# 3_phase_NPC_inverter.net
KiCad netlist of a schematic drawn in Altium Designer
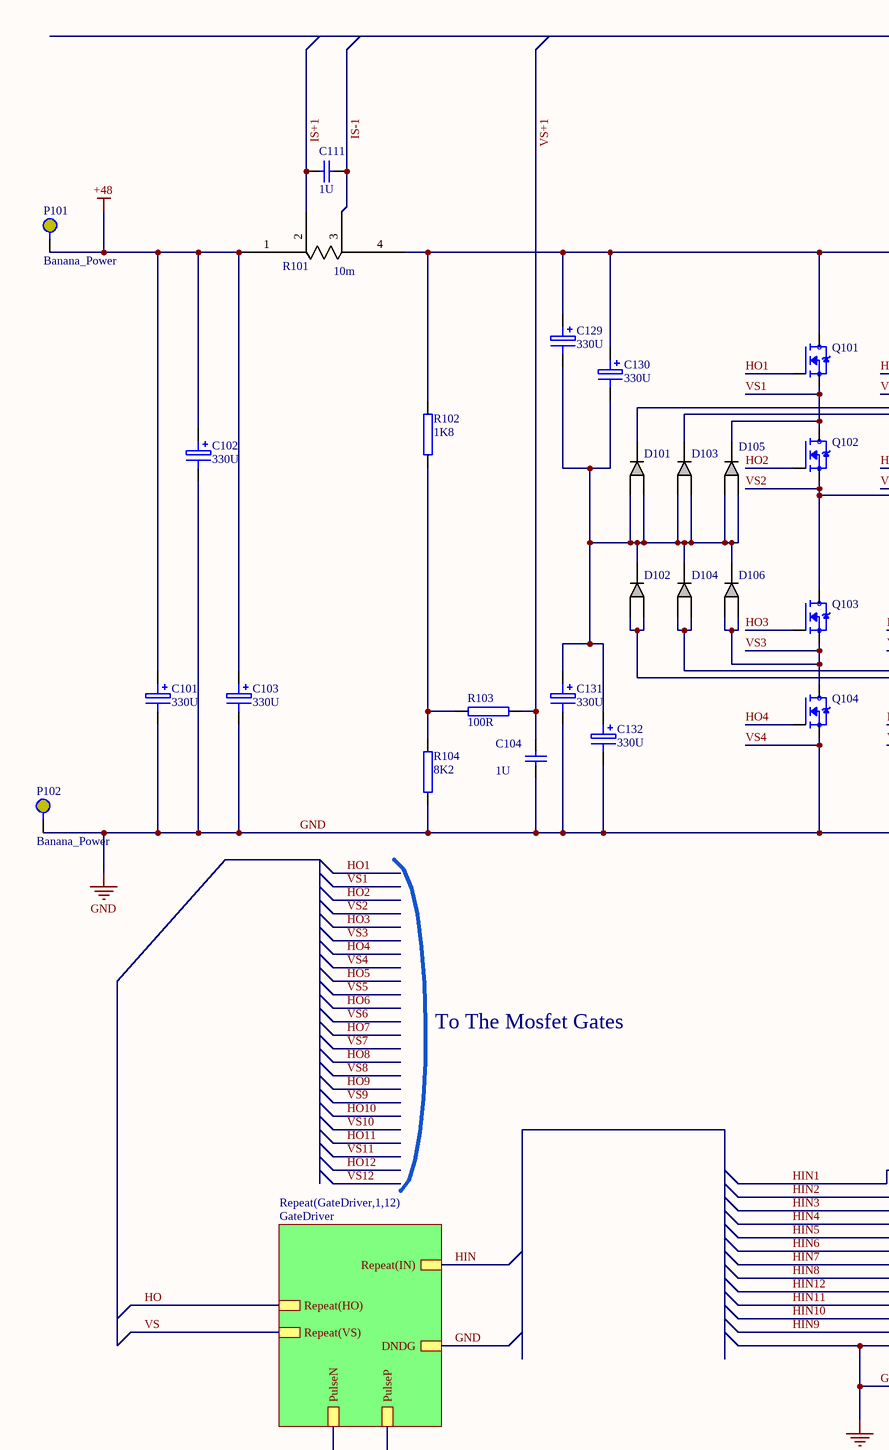
[diagram p0: 3 phase NPC inverter.SchDoc, top left]
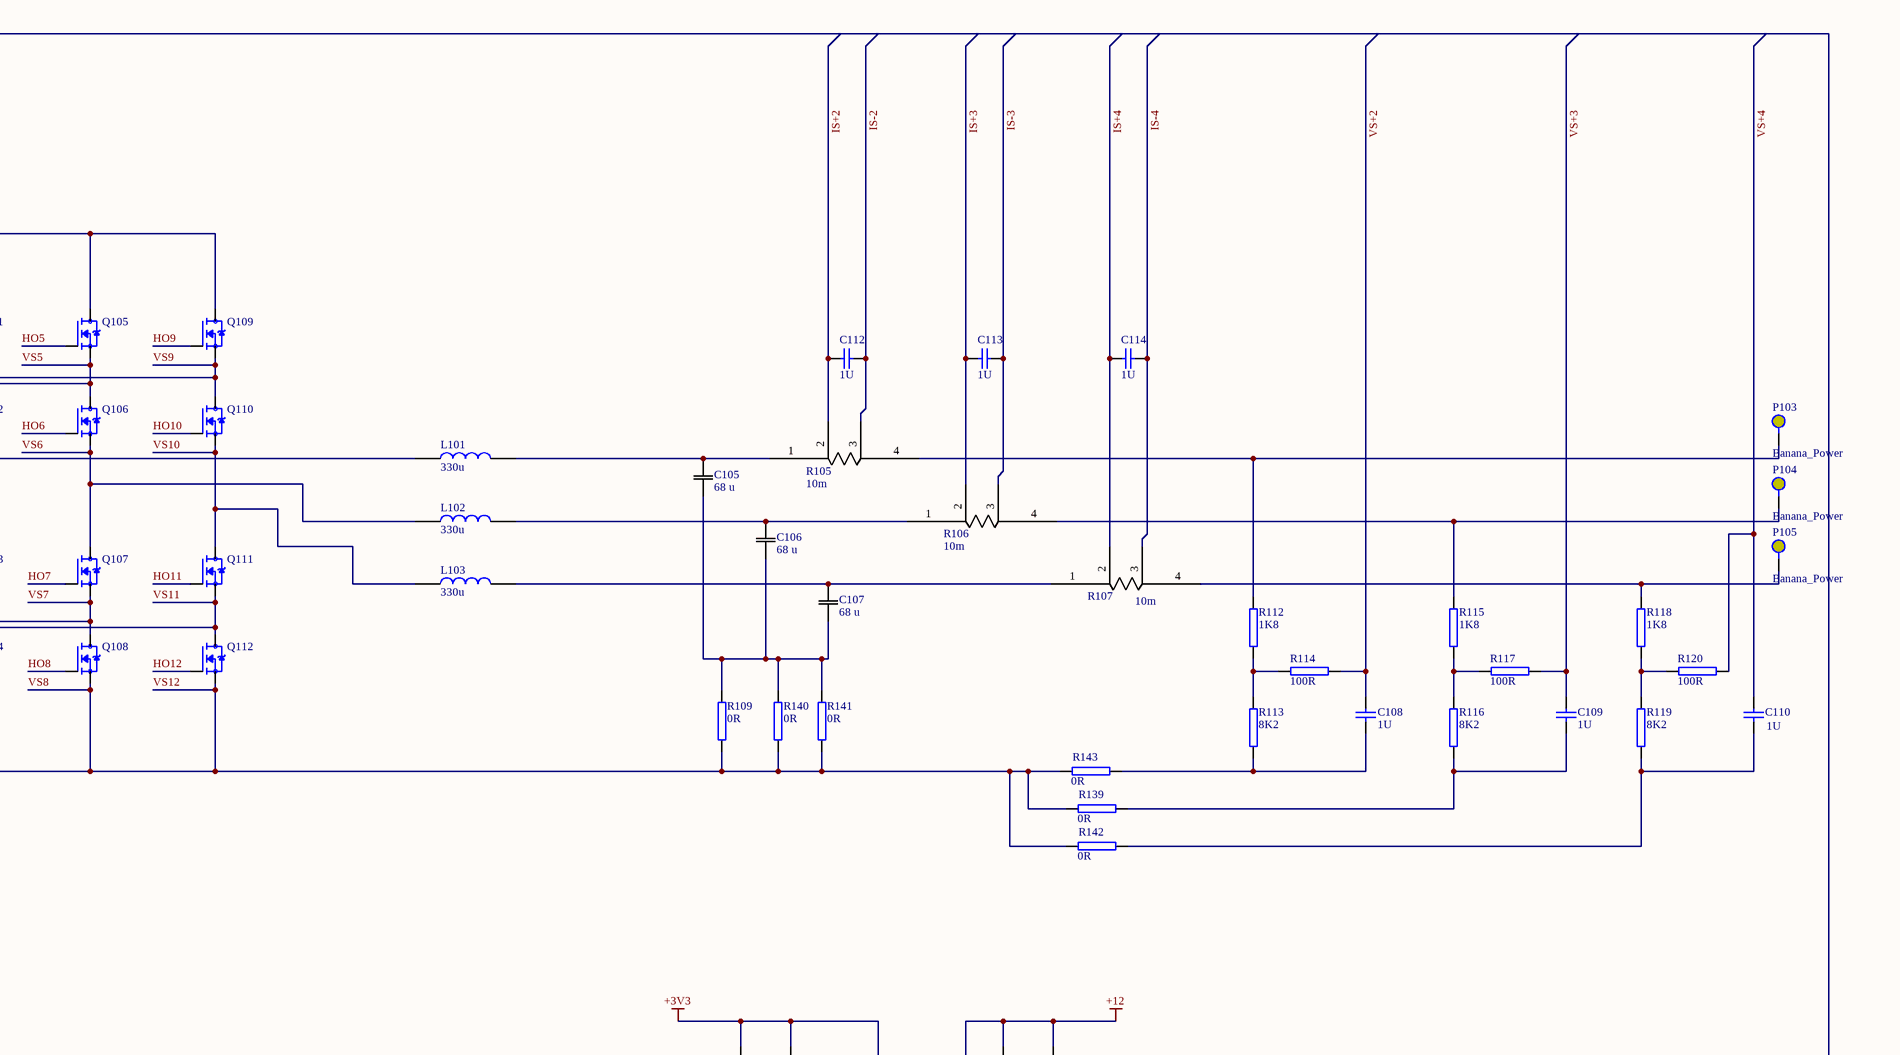
[diagram p1: 3 phase NPC inverter.SchDoc, top right]
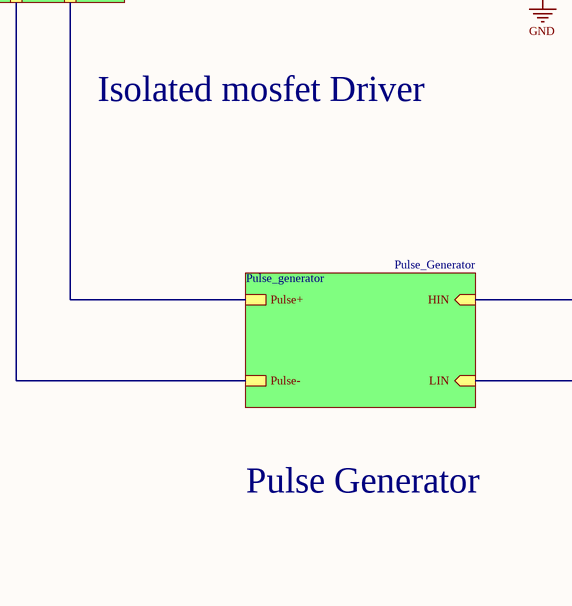
[diagram p2: 3 phase NPC inverter.SchDoc, bottom left]
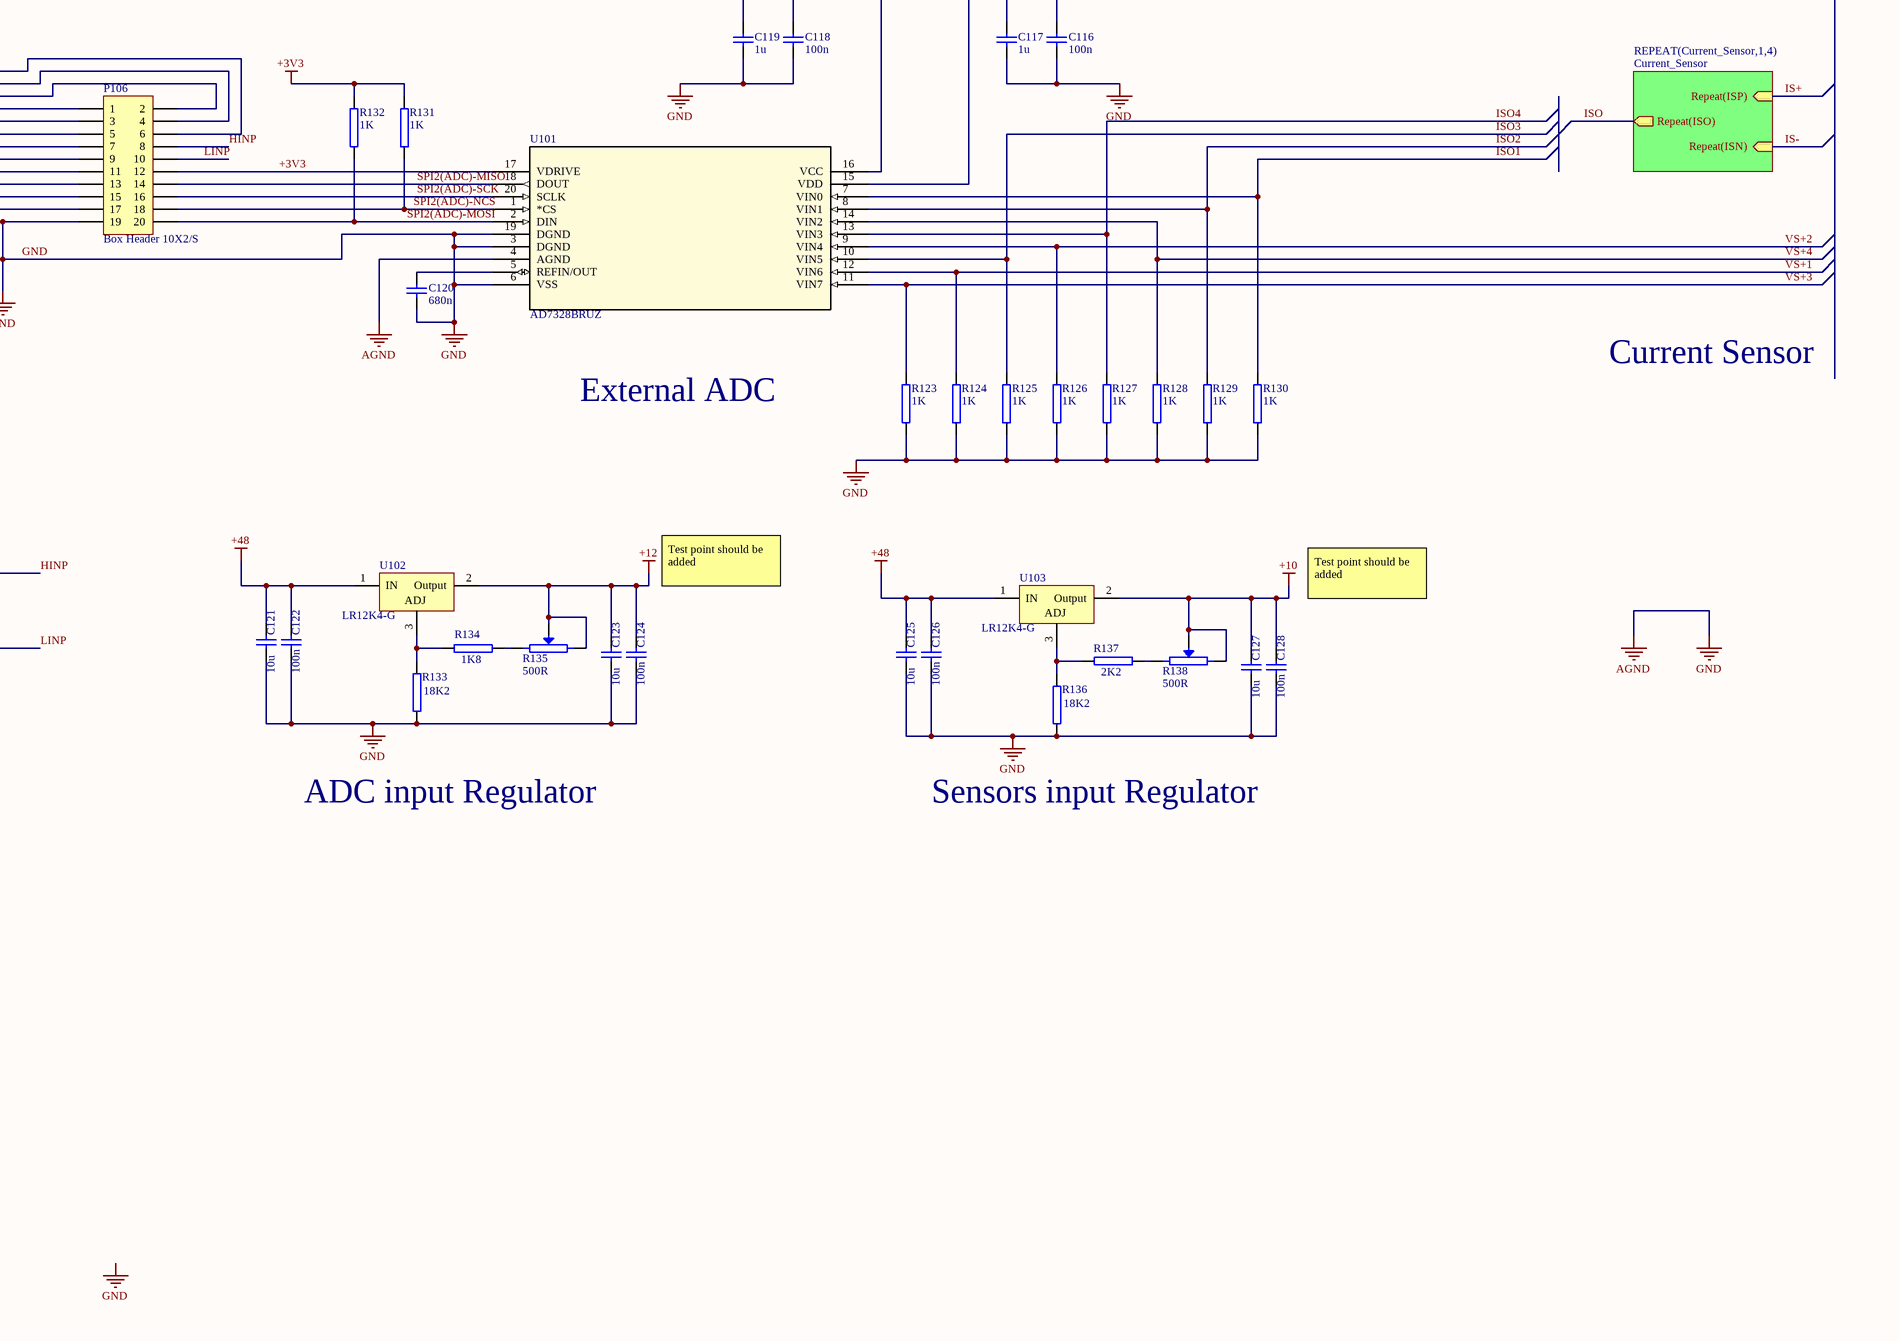
[diagram p3: 3 phase NPC inverter.SchDoc, bottom right]

(export (version "E")
  (design (tool "Eeschema 10.0.6"))
  (components
    (comp (ref "C101")
      (value "330U")
      (footprint "CAPP300-600_AUT")
      (description "Polarized Aluminum Capacitor, Through Hole, Pitch 300mil, Body 600mil (Dia)")
      (libsource (lib "Resistors and Capacitors") (part "CAPP300-600"))
    )
    (comp (ref "C102")
      (value "330U")
      (footprint "CAPP300-600_AUT")
      (description "Polarized Aluminum Capacitor, Through Hole, Pitch 300mil, Body 600mil (Dia)")
      (libsource (lib "Resistors and Capacitors") (part "CAPP300-600"))
    )
    (comp (ref "C103")
      (value "330U")
      (footprint "CAPP300-600_AUT")
      (description "Polarized Aluminum Capacitor, Through Hole, Pitch 300mil, Body 600mil (Dia)")
      (libsource (lib "Resistors and Capacitors") (part "CAPP300-600"))
    )
    (comp (ref "C104")
      (value "1U")
      (footprint "CAP_1206")
      (description "Non Polarized Capacitor, SMD, 1206")
      (libsource (lib "Resistors and Capacitors") (part "CAPN 1206"))
    )
    (comp (ref "C105")
      (value "68 u")
      (footprint "B32526R3686K000")
      (libsource (lib "ENEL709_Schematic_Library") (part "B32526R3686K000"))
    )
    (comp (ref "C106")
      (value "68 u")
      (footprint "B32526R3686K000")
      (libsource (lib "ENEL709_Schematic_Library") (part "B32526R3686K000"))
    )
    (comp (ref "C107")
      (value "68 u")
      (footprint "B32526R3686K000")
      (libsource (lib "ENEL709_Schematic_Library") (part "B32526R3686K000"))
    )
    (comp (ref "C108")
      (value "1U")
      (footprint "CAP_1206")
      (description "Non Polarized Capacitor, SMD, 1206")
      (libsource (lib "Resistors and Capacitors") (part "CAPN 1206"))
    )
    (comp (ref "C109")
      (value "1U")
      (footprint "CAP_1206")
      (description "Non Polarized Capacitor, SMD, 1206")
      (libsource (lib "Resistors and Capacitors") (part "CAPN 1206"))
    )
    (comp (ref "C110")
      (value "1U")
      (footprint "CAP_1206")
      (description "Non Polarized Capacitor, SMD, 1206")
      (libsource (lib "Resistors and Capacitors") (part "CAPN 1206"))
    )
    (comp (ref "C111")
      (value "1U")
      (footprint "CAP_1206")
      (description "Non Polarized Capacitor, SMD, 1206")
      (libsource (lib "Resistors and Capacitors") (part "CAPN 1206"))
    )
    (comp (ref "C112")
      (value "1U")
      (footprint "CAP_1206")
      (description "Non Polarized Capacitor, SMD, 1206")
      (libsource (lib "Resistors and Capacitors") (part "CAPN 1206"))
    )
    (comp (ref "C113")
      (value "1U")
      (footprint "CAP_1206")
      (description "Non Polarized Capacitor, SMD, 1206")
      (libsource (lib "Resistors and Capacitors") (part "CAPN 1206"))
    )
    (comp (ref "C114")
      (value "1U")
      (footprint "CAP_1206")
      (description "Non Polarized Capacitor, SMD, 1206")
      (libsource (lib "Resistors and Capacitors") (part "CAPN 1206"))
    )
    (comp (ref "C116")
      (value "100n")
      (footprint "CAP_1206")
      (description "Non Polarized Capacitor, SMD, 1206")
      (libsource (lib "Resistors and Capacitors") (part "CAPN 1206"))
    )
    (comp (ref "C117")
      (value "1u")
      (footprint "CAP_1206")
      (description "Non Polarized Capacitor, SMD, 1206")
      (libsource (lib "Resistors and Capacitors") (part "CAPN 1206"))
    )
    (comp (ref "C118")
      (value "100n")
      (footprint "CAP_1206")
      (description "Non Polarized Capacitor, SMD, 1206")
      (libsource (lib "Resistors and Capacitors") (part "CAPN 1206"))
    )
    (comp (ref "C119")
      (value "1u")
      (footprint "CAP_1206")
      (description "Non Polarized Capacitor, SMD, 1206")
      (libsource (lib "Resistors and Capacitors") (part "CAPN 1206"))
    )
    (comp (ref "C120")
      (value "680n")
      (footprint "CAP_1206")
      (description "Non Polarized Capacitor, SMD, 1206")
      (libsource (lib "Resistors and Capacitors") (part "CAPN 1206"))
    )
    (comp (ref "C121")
      (value "10u")
      (footprint "CAP_1206")
      (description "Non Polarized Capacitor, SMD, 1206")
      (libsource (lib "Resistors and Capacitors") (part "CAPN 1206"))
    )
    (comp (ref "C122")
      (value "100n")
      (footprint "CAP_1206")
      (description "Non Polarized Capacitor, SMD, 1206")
      (libsource (lib "Resistors and Capacitors") (part "CAPN 1206"))
    )
    (comp (ref "C123")
      (value "10u")
      (footprint "CAP_1206")
      (description "Non Polarized Capacitor, SMD, 1206")
      (libsource (lib "Resistors and Capacitors") (part "CAPN 1206"))
    )
    (comp (ref "C124")
      (value "100n")
      (footprint "CAP_1206")
      (description "Non Polarized Capacitor, SMD, 1206")
      (libsource (lib "Resistors and Capacitors") (part "CAPN 1206"))
    )
    (comp (ref "C125")
      (value "10u")
      (footprint "CAP_1206")
      (description "Non Polarized Capacitor, SMD, 1206")
      (libsource (lib "Resistors and Capacitors") (part "CAPN 1206"))
    )
    (comp (ref "C126")
      (value "100n")
      (footprint "CAP_1206")
      (description "Non Polarized Capacitor, SMD, 1206")
      (libsource (lib "Resistors and Capacitors") (part "CAPN 1206"))
    )
    (comp (ref "C127")
      (value "10u")
      (footprint "CAP_1206")
      (description "Non Polarized Capacitor, SMD, 1206")
      (libsource (lib "Resistors and Capacitors") (part "CAPN 1206"))
    )
    (comp (ref "C128")
      (value "100n")
      (footprint "CAP_1206")
      (description "Non Polarized Capacitor, SMD, 1206")
      (libsource (lib "Resistors and Capacitors") (part "CAPN 1206"))
    )
    (comp (ref "C129")
      (value "330U")
      (footprint "CAPP300-600_AUT")
      (description "Polarized Aluminum Capacitor, Through Hole, Pitch 300mil, Body 600mil (Dia)")
      (libsource (lib "Resistors and Capacitors") (part "CAPP300-600"))
    )
    (comp (ref "C130")
      (value "330U")
      (footprint "CAPP300-600_AUT")
      (description "Polarized Aluminum Capacitor, Through Hole, Pitch 300mil, Body 600mil (Dia)")
      (libsource (lib "Resistors and Capacitors") (part "CAPP300-600"))
    )
    (comp (ref "C131")
      (value "330U")
      (footprint "CAPP300-600_AUT")
      (description "Polarized Aluminum Capacitor, Through Hole, Pitch 300mil, Body 600mil (Dia)")
      (libsource (lib "Resistors and Capacitors") (part "CAPP300-600"))
    )
    (comp (ref "C132")
      (value "330U")
      (footprint "CAPP300-600_AUT")
      (description "Polarized Aluminum Capacitor, Through Hole, Pitch 300mil, Body 600mil (Dia)")
      (libsource (lib "Resistors and Capacitors") (part "CAPP300-600"))
    )
    (comp (ref "D101")
      (value "FSV20100V")
      (footprint "SOT_20100V_ONS-M")
      (libsource (lib "ENEL709_Schematic_Library") (part "FSV20100V"))
    )
    (comp (ref "D102")
      (value "FSV20100V")
      (footprint "SOT_20100V_ONS-M")
      (libsource (lib "ENEL709_Schematic_Library") (part "FSV20100V"))
    )
    (comp (ref "D103")
      (value "FSV20100V")
      (footprint "SOT_20100V_ONS-M")
      (libsource (lib "ENEL709_Schematic_Library") (part "FSV20100V"))
    )
    (comp (ref "D104")
      (value "FSV20100V")
      (footprint "SOT_20100V_ONS-M")
      (libsource (lib "ENEL709_Schematic_Library") (part "FSV20100V"))
    )
    (comp (ref "D105")
      (value "FSV20100V")
      (footprint "SOT_20100V_ONS-M")
      (libsource (lib "ENEL709_Schematic_Library") (part "FSV20100V"))
    )
    (comp (ref "D106")
      (value "FSV20100V")
      (footprint "SOT_20100V_ONS-M")
      (libsource (lib "ENEL709_Schematic_Library") (part "FSV20100V"))
    )
    (comp (ref "L101")
      (value "330u")
      (footprint "1140-331K-RC")
      (libsource (lib "ENEL709_Schematic_Library") (part "1140-331K-RC"))
    )
    (comp (ref "L102")
      (value "330u")
      (footprint "1140-331K-RC")
      (libsource (lib "ENEL709_Schematic_Library") (part "1140-331K-RC"))
    )
    (comp (ref "L103")
      (value "330u")
      (footprint "1140-331K-RC")
      (libsource (lib "ENEL709_Schematic_Library") (part "1140-331K-RC"))
    )
    (comp (ref "P101")
      (value "Banana_Power")
      (footprint "Banana_Power")
      (description "4mm pitch")
      (libsource (lib "Schlib") (part "Banana_Power"))
    )
    (comp (ref "P102")
      (value "Banana_Power")
      (footprint "Banana_Power")
      (description "4mm pitch")
      (libsource (lib "Schlib") (part "Banana_Power"))
    )
    (comp (ref "P103")
      (value "Banana_Power")
      (footprint "Banana_Power")
      (description "4mm pitch")
      (libsource (lib "Schlib") (part "Banana_Power"))
    )
    (comp (ref "P104")
      (value "Banana_Power")
      (footprint "Banana_Power")
      (description "4mm pitch")
      (libsource (lib "Schlib") (part "Banana_Power"))
    )
    (comp (ref "P105")
      (value "Banana_Power")
      (footprint "Banana_Power")
      (description "4mm pitch")
      (libsource (lib "Schlib") (part "Banana_Power"))
    )
    (comp (ref "P106")
      (value "Box Header 10X2/S")
      (footprint "FKV20SN_AUT")
      (description "Header, Box, 20 Way, 2.54mm, Straght")
      (libsource (lib "Connectors") (part "Box Header 10X2/S"))
    )
    (comp (ref "Q101")
      (value "MCTL80N20Y-TP")
      (footprint "TOLL-8L")
      (description "N-Channel 200 V 80A (Tc) 250W (Tj) Surface Mount TOLL-8L")
      (libsource (lib "Projects_2025") (part "MCTL80N20Y-TP"))
    )
    (comp (ref "Q102")
      (value "MCTL80N20Y-TP")
      (footprint "TOLL-8L")
      (description "N-Channel 200 V 80A (Tc) 250W (Tj) Surface Mount TOLL-8L")
      (libsource (lib "Projects_2025") (part "MCTL80N20Y-TP"))
    )
    (comp (ref "Q103")
      (value "MCTL80N20Y-TP")
      (footprint "TOLL-8L")
      (description "N-Channel 200 V 80A (Tc) 250W (Tj) Surface Mount TOLL-8L")
      (libsource (lib "Projects_2025") (part "MCTL80N20Y-TP"))
    )
    (comp (ref "Q104")
      (value "MCTL80N20Y-TP")
      (footprint "TOLL-8L")
      (description "N-Channel 200 V 80A (Tc) 250W (Tj) Surface Mount TOLL-8L")
      (libsource (lib "Projects_2025") (part "MCTL80N20Y-TP"))
    )
    (comp (ref "Q105")
      (value "MCTL80N20Y-TP")
      (footprint "TOLL-8L")
      (description "N-Channel 200 V 80A (Tc) 250W (Tj) Surface Mount TOLL-8L")
      (libsource (lib "Projects_2025") (part "MCTL80N20Y-TP"))
    )
    (comp (ref "Q106")
      (value "MCTL80N20Y-TP")
      (footprint "TOLL-8L")
      (description "N-Channel 200 V 80A (Tc) 250W (Tj) Surface Mount TOLL-8L")
      (libsource (lib "Projects_2025") (part "MCTL80N20Y-TP"))
    )
    (comp (ref "Q107")
      (value "MCTL80N20Y-TP")
      (footprint "TOLL-8L")
      (description "N-Channel 200 V 80A (Tc) 250W (Tj) Surface Mount TOLL-8L")
      (libsource (lib "Projects_2025") (part "MCTL80N20Y-TP"))
    )
    (comp (ref "Q108")
      (value "MCTL80N20Y-TP")
      (footprint "TOLL-8L")
      (description "N-Channel 200 V 80A (Tc) 250W (Tj) Surface Mount TOLL-8L")
      (libsource (lib "Projects_2025") (part "MCTL80N20Y-TP"))
    )
    (comp (ref "Q109")
      (value "MCTL80N20Y-TP")
      (footprint "TOLL-8L")
      (description "N-Channel 200 V 80A (Tc) 250W (Tj) Surface Mount TOLL-8L")
      (libsource (lib "Projects_2025") (part "MCTL80N20Y-TP"))
    )
    (comp (ref "Q110")
      (value "MCTL80N20Y-TP")
      (footprint "TOLL-8L")
      (description "N-Channel 200 V 80A (Tc) 250W (Tj) Surface Mount TOLL-8L")
      (libsource (lib "Projects_2025") (part "MCTL80N20Y-TP"))
    )
    (comp (ref "Q111")
      (value "MCTL80N20Y-TP")
      (footprint "TOLL-8L")
      (description "N-Channel 200 V 80A (Tc) 250W (Tj) Surface Mount TOLL-8L")
      (libsource (lib "Projects_2025") (part "MCTL80N20Y-TP"))
    )
    (comp (ref "Q112")
      (value "MCTL80N20Y-TP")
      (footprint "TOLL-8L")
      (description "N-Channel 200 V 80A (Tc) 250W (Tj) Surface Mount TOLL-8L")
      (libsource (lib "Projects_2025") (part "MCTL80N20Y-TP"))
    )
    (comp (ref "R101")
      (value "10m")
      (footprint "WSL3673R_002-01")
      (description "Current Shunt \r\nKelvin 4W 0.002- 0.01")
      (libsource (lib "Projects_2025") (part "WSL3673R-01"))
    )
    (comp (ref "R102")
      (value "1K8")
      (footprint "RES_1206")
      (description "Resistor, SMD, 1206")
      (libsource (lib "Resistors and Capacitors") (part "Resistor 1206"))
    )
    (comp (ref "R103")
      (value "100R")
      (footprint "RES_1206")
      (description "Resistor, SMD, 1206")
      (libsource (lib "Resistors and Capacitors") (part "Resistor 1206"))
    )
    (comp (ref "R104")
      (value "8K2")
      (footprint "RES_1206")
      (description "Resistor, SMD, 1206")
      (libsource (lib "Resistors and Capacitors") (part "Resistor 1206"))
    )
    (comp (ref "R105")
      (value "10m")
      (footprint "WSL3673R_002-01")
      (description "Current Shunt \r\nKelvin 4W 0.002- 0.01")
      (libsource (lib "Projects_2025") (part "WSL3673R-01"))
    )
    (comp (ref "R106")
      (value "10m")
      (footprint "WSL3673R_002-01")
      (description "Current Shunt \r\nKelvin 4W 0.002- 0.01")
      (libsource (lib "Projects_2025") (part "WSL3673R-01"))
    )
    (comp (ref "R107")
      (value "10m")
      (footprint "WSL3673R_002-01")
      (description "Current Shunt \r\nKelvin 4W 0.002- 0.01")
      (libsource (lib "Projects_2025") (part "WSL3673R-01"))
    )
    (comp (ref "R109")
      (value "0R")
      (footprint "RES_1206")
      (description "Resistor, SMD, 1206")
      (libsource (lib "Resistors and Capacitors") (part "Resistor 1206"))
    )
    (comp (ref "R112")
      (value "1K8")
      (footprint "RES_1206")
      (description "Resistor, SMD, 1206")
      (libsource (lib "Resistors and Capacitors") (part "Resistor 1206"))
    )
    (comp (ref "R113")
      (value "8K2")
      (footprint "RES_1206")
      (description "Resistor, SMD, 1206")
      (libsource (lib "Resistors and Capacitors") (part "Resistor 1206"))
    )
    (comp (ref "R114")
      (value "100R")
      (footprint "RES_1206")
      (description "Resistor, SMD, 1206")
      (libsource (lib "Resistors and Capacitors") (part "Resistor 1206"))
    )
    (comp (ref "R115")
      (value "1K8")
      (footprint "RES_1206")
      (description "Resistor, SMD, 1206")
      (libsource (lib "Resistors and Capacitors") (part "Resistor 1206"))
    )
    (comp (ref "R116")
      (value "8K2")
      (footprint "RES_1206")
      (description "Resistor, SMD, 1206")
      (libsource (lib "Resistors and Capacitors") (part "Resistor 1206"))
    )
    (comp (ref "R117")
      (value "100R")
      (footprint "RES_1206")
      (description "Resistor, SMD, 1206")
      (libsource (lib "Resistors and Capacitors") (part "Resistor 1206"))
    )
    (comp (ref "R118")
      (value "1K8")
      (footprint "RES_1206")
      (description "Resistor, SMD, 1206")
      (libsource (lib "Resistors and Capacitors") (part "Resistor 1206"))
    )
    (comp (ref "R119")
      (value "8K2")
      (footprint "RES_1206")
      (description "Resistor, SMD, 1206")
      (libsource (lib "Resistors and Capacitors") (part "Resistor 1206"))
    )
    (comp (ref "R120")
      (value "100R")
      (footprint "RES_1206")
      (description "Resistor, SMD, 1206")
      (libsource (lib "Resistors and Capacitors") (part "Resistor 1206"))
    )
    (comp (ref "R123")
      (value "1K")
      (footprint "RES_1206")
      (description "Resistor, SMD, 1206")
      (libsource (lib "Resistors and Capacitors") (part "Resistor 1206"))
    )
    (comp (ref "R124")
      (value "1K")
      (footprint "RES_1206")
      (description "Resistor, SMD, 1206")
      (libsource (lib "Resistors and Capacitors") (part "Resistor 1206"))
    )
    (comp (ref "R125")
      (value "1K")
      (footprint "RES_1206")
      (description "Resistor, SMD, 1206")
      (libsource (lib "Resistors and Capacitors") (part "Resistor 1206"))
    )
    (comp (ref "R126")
      (value "1K")
      (footprint "RES_1206")
      (description "Resistor, SMD, 1206")
      (libsource (lib "Resistors and Capacitors") (part "Resistor 1206"))
    )
    (comp (ref "R127")
      (value "1K")
      (footprint "RES_1206")
      (description "Resistor, SMD, 1206")
      (libsource (lib "Resistors and Capacitors") (part "Resistor 1206"))
    )
    (comp (ref "R128")
      (value "1K")
      (footprint "RES_1206")
      (description "Resistor, SMD, 1206")
      (libsource (lib "Resistors and Capacitors") (part "Resistor 1206"))
    )
    (comp (ref "R129")
      (value "1K")
      (footprint "RES_1206")
      (description "Resistor, SMD, 1206")
      (libsource (lib "Resistors and Capacitors") (part "Resistor 1206"))
    )
    (comp (ref "R130")
      (value "1K")
      (footprint "RES_1206")
      (description "Resistor, SMD, 1206")
      (libsource (lib "Resistors and Capacitors") (part "Resistor 1206"))
    )
    (comp (ref "R131")
      (value "1K")
      (footprint "RES_1206")
      (description "Resistor, SMD, 1206")
      (libsource (lib "Resistors and Capacitors") (part "Resistor 1206"))
    )
    (comp (ref "R132")
      (value "1K")
      (footprint "RES_1206")
      (description "Resistor, SMD, 1206")
      (libsource (lib "Resistors and Capacitors") (part "Resistor 1206"))
    )
    (comp (ref "R133")
      (value "18K2")
      (footprint "RES_1206")
      (description "Resistor, SMD, 1206")
      (libsource (lib "Resistors and Capacitors") (part "Resistor 1206"))
    )
    (comp (ref "R134")
      (value "1K8")
      (footprint "RES_1206")
      (description "Resistor, SMD, 1206")
      (libsource (lib "Resistors and Capacitors") (part "Resistor 1206"))
    )
    (comp (ref "R135")
      (value "500R")
      (footprint "3296W")
      (libsource (lib "Potentiometers") (part "3296W-1-104LF"))
    )
    (comp (ref "R136")
      (value "18K2")
      (footprint "RES_1206")
      (description "Resistor, SMD, 1206")
      (libsource (lib "Resistors and Capacitors") (part "Resistor 1206"))
    )
    (comp (ref "R137")
      (value "2K2")
      (footprint "RES_1206")
      (description "Resistor, SMD, 1206")
      (libsource (lib "Resistors and Capacitors") (part "Resistor 1206"))
    )
    (comp (ref "R138")
      (value "500R")
      (footprint "3296W")
      (libsource (lib "Potentiometers") (part "3296W-1-104LF"))
    )
    (comp (ref "R139")
      (value "0R")
      (footprint "RES_1206")
      (description "Resistor, SMD, 1206")
      (libsource (lib "Resistors and Capacitors") (part "Resistor 1206"))
    )
    (comp (ref "R140")
      (value "0R")
      (footprint "RES_1206")
      (description "Resistor, SMD, 1206")
      (libsource (lib "Resistors and Capacitors") (part "Resistor 1206"))
    )
    (comp (ref "R141")
      (value "0R")
      (footprint "RES_1206")
      (description "Resistor, SMD, 1206")
      (libsource (lib "Resistors and Capacitors") (part "Resistor 1206"))
    )
    (comp (ref "R142")
      (value "0R")
      (footprint "RES_1206")
      (description "Resistor, SMD, 1206")
      (libsource (lib "Resistors and Capacitors") (part "Resistor 1206"))
    )
    (comp (ref "R143")
      (value "0R")
      (footprint "RES_1206")
      (description "Resistor, SMD, 1206")
      (libsource (lib "Resistors and Capacitors") (part "Resistor 1206"))
    )
    (comp (ref "U101")
      (value "AD7328BRUZ")
      (footprint "TSSOP20_44")
      (description "ADC 12 Bit\r\nPackage TSSOP20")
      (libsource (lib "Projects_2025") (part "AD7328BRUZ"))
    )
    (comp (ref "U102")
      (value "LR12K4-G")
      (footprint "D PAK (TO-252-3)")
      (description "Adj Positive Regulator \r\nLinear. 12V dropout V. \r\n2W")
      (libsource (lib "Projects_2025") (part "LR12K4-G"))
    )
    (comp (ref "U103")
      (value "LR12K4-G")
      (footprint "D PAK (TO-252-3)")
      (description "Adj Positive Regulator \r\nLinear. 12V dropout V. \r\n2W")
      (libsource (lib "Projects_2025") (part "LR12K4-G"))
    )
  )
  (nets
    (net (code "1") (name "+3V3") (class "Default")
      (node (ref "C118") (pin "2") (pinfunction "2_2") (pintype "passive"))
      (node (ref "C119") (pin "2") (pinfunction "2_2") (pintype "passive"))
      (node (ref "P106") (pin "12") (pinfunction "12_12") (pintype "passive"))
      (node (ref "R131") (pin "2") (pinfunction "2_2") (pintype "passive"))
      (node (ref "R132") (pin "2") (pinfunction "2_2") (pintype "passive"))
      (node (ref "U101") (pin "16") (pinfunction "VCC_16") (pintype "power_in"))
      (node (ref "U101") (pin "17") (pinfunction "VDRIVE_17") (pintype "power_in"))
    )
    (net (code "2") (name "+10") (class "Default")
      (node (ref "C127") (pin "2") (pinfunction "2_2") (pintype "passive"))
      (node (ref "C128") (pin "2") (pinfunction "2_2") (pintype "passive"))
      (node (ref "R138") (pin "2") (pinfunction "BOT_2") (pintype "passive"))
      (node (ref "R138") (pin "W") (pinfunction "TAP_W") (pintype "passive"))
      (node (ref "U103") (pin "2") (pinfunction "Output_2") (pintype "power_in"))
    )
    (net (code "3") (name "+12") (class "Default")
      (node (ref "C116") (pin "2") (pinfunction "2_2") (pintype "passive"))
      (node (ref "C117") (pin "2") (pinfunction "2_2") (pintype "passive"))
      (node (ref "C123") (pin "2") (pinfunction "2_2") (pintype "passive"))
      (node (ref "C124") (pin "2") (pinfunction "2_2") (pintype "passive"))
      (node (ref "R135") (pin "2") (pinfunction "BOT_2") (pintype "passive"))
      (node (ref "R135") (pin "W") (pinfunction "TAP_W") (pintype "passive"))
      (node (ref "U101") (pin "15") (pinfunction "VDD_15") (pintype "power_in"))
      (node (ref "U102") (pin "2") (pinfunction "Output_2") (pintype "power_in"))
    )
    (net (code "4") (name "+48") (class "Default")
      (node (ref "C101") (pin "1") (pinfunction "1_1") (pintype "passive"))
      (node (ref "C102") (pin "1") (pinfunction "1_1") (pintype "passive"))
      (node (ref "C103") (pin "1") (pinfunction "1_1") (pintype "passive"))
      (node (ref "C121") (pin "2") (pinfunction "2_2") (pintype "passive"))
      (node (ref "C122") (pin "2") (pinfunction "2_2") (pintype "passive"))
      (node (ref "C125") (pin "2") (pinfunction "2_2") (pintype "passive"))
      (node (ref "C126") (pin "2") (pinfunction "2_2") (pintype "passive"))
      (node (ref "P101") (pin "1") (pintype "passive"))
      (node (ref "R101") (pin "1") (pinfunction "1_1") (pintype "passive"))
      (node (ref "U102") (pin "1") (pinfunction "IN_1") (pintype "power_in"))
      (node (ref "U103") (pin "1") (pinfunction "IN_1") (pintype "power_in"))
    )
    (net (code "6") (name "/HIN1") (class "Default")
      (node (ref "P106") (pin "6") (pinfunction "6_6") (pintype "passive"))
    )
    (net (code "7") (name "/HIN2") (class "Default")
      (node (ref "P106") (pin "4") (pinfunction "4_4") (pintype "passive"))
    )
    (net (code "8") (name "/HIN3") (class "Default")
      (node (ref "P106") (pin "2") (pinfunction "2_2") (pintype "passive"))
    )
    (net (code "9") (name "/HIN4") (class "Default")
      (node (ref "P106") (pin "1") (pinfunction "1_1") (pintype "passive"))
    )
    (net (code "10") (name "/HIN5") (class "Default")
      (node (ref "P106") (pin "3") (pinfunction "3_3") (pintype "passive"))
    )
    (net (code "11") (name "/HIN6") (class "Default")
      (node (ref "P106") (pin "5") (pinfunction "5_5") (pintype "passive"))
    )
    (net (code "12") (name "/HIN7") (class "Default")
      (node (ref "P106") (pin "7") (pinfunction "7_7") (pintype "passive"))
    )
    (net (code "13") (name "/HIN8") (class "Default")
      (node (ref "P106") (pin "9") (pinfunction "9_9") (pintype "passive"))
    )
    (net (code "14") (name "/HIN9") (class "Default")
      (node (ref "P106") (pin "17") (pinfunction "17_17") (pintype "passive"))
    )
    (net (code "15") (name "/HIN10") (class "Default")
      (node (ref "P106") (pin "15") (pinfunction "15_15") (pintype "passive"))
    )
    (net (code "16") (name "/HIN11") (class "Default")
      (node (ref "P106") (pin "13") (pinfunction "13_13") (pintype "passive"))
    )
    (net (code "17") (name "/HIN12") (class "Default")
      (node (ref "P106") (pin "11") (pinfunction "11_11") (pintype "passive"))
    )
    (net (code "18") (name "/HINP") (class "Default")
      (node (ref "P106") (pin "8") (pinfunction "8_8") (pintype "passive"))
    )
    (net (code "20") (name "/HO1") (class "Default")
      (node (ref "Q101") (pin "1") (pinfunction "G_1") (pintype "passive"))
    )
    (net (code "21") (name "/HO2") (class "Default")
      (node (ref "Q102") (pin "1") (pinfunction "G_1") (pintype "passive"))
    )
    (net (code "22") (name "/HO3") (class "Default")
      (node (ref "Q103") (pin "1") (pinfunction "G_1") (pintype "passive"))
    )
    (net (code "23") (name "/HO4") (class "Default")
      (node (ref "Q104") (pin "1") (pinfunction "G_1") (pintype "passive"))
    )
    (net (code "24") (name "/HO5") (class "Default")
      (node (ref "Q105") (pin "1") (pinfunction "G_1") (pintype "passive"))
    )
    (net (code "25") (name "/HO6") (class "Default")
      (node (ref "Q106") (pin "1") (pinfunction "G_1") (pintype "passive"))
    )
    (net (code "26") (name "/HO7") (class "Default")
      (node (ref "Q107") (pin "1") (pinfunction "G_1") (pintype "passive"))
    )
    (net (code "27") (name "/HO8") (class "Default")
      (node (ref "Q108") (pin "1") (pinfunction "G_1") (pintype "passive"))
    )
    (net (code "28") (name "/HO9") (class "Default")
      (node (ref "Q109") (pin "1") (pinfunction "G_1") (pintype "passive"))
    )
    (net (code "29") (name "/HO10") (class "Default")
      (node (ref "Q110") (pin "1") (pinfunction "G_1") (pintype "passive"))
    )
    (net (code "30") (name "/HO11") (class "Default")
      (node (ref "Q111") (pin "1") (pinfunction "G_1") (pintype "passive"))
    )
    (net (code "31") (name "/HO12") (class "Default")
      (node (ref "Q112") (pin "1") (pinfunction "G_1") (pintype "passive"))
    )
    (net (code "33") (name "/IS+1") (class "Default")
      (node (ref "C111") (pin "2") (pinfunction "2_2") (pintype "passive"))
      (node (ref "R101") (pin "2") (pinfunction "2_2") (pintype "passive"))
    )
    (net (code "34") (name "/IS+2") (class "Default")
      (node (ref "C112") (pin "2") (pinfunction "2_2") (pintype "passive"))
      (node (ref "R105") (pin "2") (pinfunction "2_2") (pintype "passive"))
    )
    (net (code "35") (name "/IS+3") (class "Default")
      (node (ref "C113") (pin "2") (pinfunction "2_2") (pintype "passive"))
      (node (ref "R106") (pin "2") (pinfunction "2_2") (pintype "passive"))
    )
    (net (code "36") (name "/IS+4") (class "Default")
      (node (ref "C114") (pin "2") (pinfunction "2_2") (pintype "passive"))
      (node (ref "R107") (pin "2") (pinfunction "2_2") (pintype "passive"))
    )
    (net (code "38") (name "/IS-1") (class "Default")
      (node (ref "C111") (pin "1") (pinfunction "1_1") (pintype "passive"))
      (node (ref "R101") (pin "3") (pinfunction "3_3") (pintype "passive"))
    )
    (net (code "39") (name "/IS-2") (class "Default")
      (node (ref "C112") (pin "1") (pinfunction "1_1") (pintype "passive"))
      (node (ref "R105") (pin "3") (pinfunction "3_3") (pintype "passive"))
    )
    (net (code "40") (name "/IS-3") (class "Default")
      (node (ref "C113") (pin "1") (pinfunction "1_1") (pintype "passive"))
      (node (ref "R106") (pin "3") (pinfunction "3_3") (pintype "passive"))
    )
    (net (code "41") (name "/IS-4") (class "Default")
      (node (ref "C114") (pin "1") (pinfunction "1_1") (pintype "passive"))
      (node (ref "R107") (pin "3") (pinfunction "3_3") (pintype "passive"))
    )
    (net (code "43") (name "/ISO1") (class "Default")
      (node (ref "R130") (pin "2") (pinfunction "2_2") (pintype "passive"))
      (node (ref "U101") (pin "7") (pinfunction "VIN0_7") (pintype "input"))
    )
    (net (code "44") (name "/ISO2") (class "Default")
      (node (ref "R129") (pin "2") (pinfunction "2_2") (pintype "passive"))
      (node (ref "U101") (pin "8") (pinfunction "VIN1_8") (pintype "input"))
    )
    (net (code "45") (name "/ISO3") (class "Default")
      (node (ref "R125") (pin "2") (pinfunction "2_2") (pintype "passive"))
      (node (ref "U101") (pin "10") (pinfunction "VIN5_10") (pintype "input"))
    )
    (net (code "46") (name "/ISO4") (class "Default")
      (node (ref "R127") (pin "2") (pinfunction "2_2") (pintype "passive"))
      (node (ref "U101") (pin "13") (pinfunction "VIN3_13") (pintype "input"))
    )
    (net (code "47") (name "/LINP") (class "Default")
      (node (ref "P106") (pin "10") (pinfunction "10_10") (pintype "passive"))
    )
    (net (code "50") (name "/SPI2(ADC)-MISO") (class "Default")
      (node (ref "P106") (pin "14") (pinfunction "14_14") (pintype "passive"))
      (node (ref "U101") (pin "18") (pinfunction "DOUT_18") (pintype "output"))
    )
    (net (code "51") (name "/SPI2(ADC)-MOSI") (class "Default")
      (node (ref "P106") (pin "20") (pinfunction "20_20") (pintype "passive"))
      (node (ref "R132") (pin "1") (pinfunction "1_1") (pintype "passive"))
      (node (ref "U101") (pin "2") (pinfunction "DIN_2") (pintype "input"))
    )
    (net (code "52") (name "/SPI2(ADC)-NCS") (class "Default")
      (node (ref "P106") (pin "18") (pinfunction "18_18") (pintype "passive"))
      (node (ref "R131") (pin "1") (pinfunction "1_1") (pintype "passive"))
      (node (ref "U101") (pin "1") (pinfunction "*CS_1") (pintype "input"))
    )
    (net (code "53") (name "/SPI2(ADC)-SCK") (class "Default")
      (node (ref "P106") (pin "16") (pinfunction "16_16") (pintype "passive"))
      (node (ref "U101") (pin "20") (pinfunction "SCLK_20") (pintype "input"))
    )
    (net (code "55") (name "/VS+1") (class "Default")
      (node (ref "C104") (pin "2") (pinfunction "2_2") (pintype "passive"))
      (node (ref "R103") (pin "1") (pinfunction "1_1") (pintype "passive"))
      (node (ref "R124") (pin "2") (pinfunction "2_2") (pintype "passive"))
      (node (ref "U101") (pin "12") (pinfunction "VIN6_12") (pintype "input"))
    )
    (net (code "56") (name "/VS+2") (class "Default")
      (node (ref "C108") (pin "2") (pinfunction "2_2") (pintype "passive"))
      (node (ref "R114") (pin "1") (pinfunction "1_1") (pintype "passive"))
      (node (ref "R126") (pin "2") (pinfunction "2_2") (pintype "passive"))
      (node (ref "U101") (pin "9") (pinfunction "VIN4_9") (pintype "input"))
    )
    (net (code "57") (name "/VS+3") (class "Default")
      (node (ref "C109") (pin "2") (pinfunction "2_2") (pintype "passive"))
      (node (ref "R117") (pin "1") (pinfunction "1_1") (pintype "passive"))
      (node (ref "R123") (pin "2") (pinfunction "2_2") (pintype "passive"))
      (node (ref "U101") (pin "11") (pinfunction "VIN7_11") (pintype "input"))
    )
    (net (code "58") (name "/VS+4") (class "Default")
      (node (ref "C110") (pin "2") (pinfunction "2_2") (pintype "passive"))
      (node (ref "R120") (pin "1") (pinfunction "1_1") (pintype "passive"))
      (node (ref "R128") (pin "2") (pinfunction "2_2") (pintype "passive"))
      (node (ref "U101") (pin "14") (pinfunction "VIN2_14") (pintype "input"))
    )
    (net (code "59") (name "/VS1") (class "Default")
      (node (ref "D105") (pin "3") (pinfunction "C_3") (pintype "passive"))
      (node (ref "Q101") (pin "2") (pinfunction "S_2") (pintype "passive"))
      (node (ref "Q102") (pin "3") (pinfunction "D_3") (pintype "passive"))
    )
    (net (code "60") (name "/VS2") (class "Default")
      (node (ref "L101") (pin "1") (pinfunction "1_1") (pintype "passive"))
      (node (ref "Q102") (pin "2") (pinfunction "S_2") (pintype "passive"))
      (node (ref "Q103") (pin "3") (pinfunction "D_3") (pintype "passive"))
    )
    (net (code "61") (name "/VS3") (class "Default")
      (node (ref "D106") (pin "1") (pinfunction "A_1") (pintype "passive"))
      (node (ref "D106") (pin "2") (pinfunction "A_2") (pintype "passive"))
      (node (ref "Q103") (pin "2") (pinfunction "S_2") (pintype "passive"))
      (node (ref "Q104") (pin "3") (pinfunction "D_3") (pintype "passive"))
    )
    (net (code "62") (name "/VS5") (class "Default")
      (node (ref "D103") (pin "3") (pinfunction "C_3") (pintype "passive"))
      (node (ref "Q105") (pin "2") (pinfunction "S_2") (pintype "passive"))
      (node (ref "Q106") (pin "3") (pinfunction "D_3") (pintype "passive"))
    )
    (net (code "63") (name "/VS6") (class "Default")
      (node (ref "L102") (pin "1") (pinfunction "1_1") (pintype "passive"))
      (node (ref "Q106") (pin "2") (pinfunction "S_2") (pintype "passive"))
      (node (ref "Q107") (pin "3") (pinfunction "D_3") (pintype "passive"))
    )
    (net (code "64") (name "/VS7") (class "Default")
      (node (ref "D104") (pin "1") (pinfunction "A_1") (pintype "passive"))
      (node (ref "D104") (pin "2") (pinfunction "A_2") (pintype "passive"))
      (node (ref "Q107") (pin "2") (pinfunction "S_2") (pintype "passive"))
      (node (ref "Q108") (pin "3") (pinfunction "D_3") (pintype "passive"))
    )
    (net (code "65") (name "/VS9") (class "Default")
      (node (ref "D101") (pin "3") (pinfunction "C_3") (pintype "passive"))
      (node (ref "Q109") (pin "2") (pinfunction "S_2") (pintype "passive"))
      (node (ref "Q110") (pin "3") (pinfunction "D_3") (pintype "passive"))
    )
    (net (code "66") (name "/VS10") (class "Default")
      (node (ref "L103") (pin "1") (pinfunction "1_1") (pintype "passive"))
      (node (ref "Q110") (pin "2") (pinfunction "S_2") (pintype "passive"))
      (node (ref "Q111") (pin "3") (pinfunction "D_3") (pintype "passive"))
    )
    (net (code "67") (name "/VS11") (class "Default")
      (node (ref "D102") (pin "1") (pinfunction "A_1") (pintype "passive"))
      (node (ref "D102") (pin "2") (pinfunction "A_2") (pintype "passive"))
      (node (ref "Q111") (pin "2") (pinfunction "S_2") (pintype "passive"))
      (node (ref "Q112") (pin "3") (pinfunction "D_3") (pintype "passive"))
    )
    (net (code "68") (name "AGND") (class "Default")
      (node (ref "C101") (pin "2") (pinfunction "2_2") (pintype "passive"))
      (node (ref "C102") (pin "2") (pinfunction "2_2") (pintype "passive"))
      (node (ref "C103") (pin "2") (pinfunction "2_2") (pintype "passive"))
      (node (ref "C104") (pin "1") (pinfunction "1_1") (pintype "passive"))
      (node (ref "C116") (pin "1") (pinfunction "1_1") (pintype "passive"))
      (node (ref "C117") (pin "1") (pinfunction "1_1") (pintype "passive"))
      (node (ref "C118") (pin "1") (pinfunction "1_1") (pintype "passive"))
      (node (ref "C119") (pin "1") (pinfunction "1_1") (pintype "passive"))
      (node (ref "C120") (pin "1") (pinfunction "1_1") (pintype "passive"))
      (node (ref "C121") (pin "1") (pinfunction "1_1") (pintype "passive"))
      (node (ref "C122") (pin "1") (pinfunction "1_1") (pintype "passive"))
      (node (ref "C123") (pin "1") (pinfunction "1_1") (pintype "passive"))
      (node (ref "C124") (pin "1") (pinfunction "1_1") (pintype "passive"))
      (node (ref "C125") (pin "1") (pinfunction "1_1") (pintype "passive"))
      (node (ref "C126") (pin "1") (pinfunction "1_1") (pintype "passive"))
      (node (ref "C127") (pin "1") (pinfunction "1_1") (pintype "passive"))
      (node (ref "C128") (pin "1") (pinfunction "1_1") (pintype "passive"))
      (node (ref "C131") (pin "2") (pinfunction "2_2") (pintype "passive"))
      (node (ref "C132") (pin "2") (pinfunction "2_2") (pintype "passive"))
      (node (ref "P102") (pin "1") (pintype "passive"))
      (node (ref "P106") (pin "19") (pinfunction "19_19") (pintype "passive"))
      (node (ref "Q104") (pin "2") (pinfunction "S_2") (pintype "passive"))
      (node (ref "Q108") (pin "2") (pinfunction "S_2") (pintype "passive"))
      (node (ref "Q112") (pin "2") (pinfunction "S_2") (pintype "passive"))
      (node (ref "R104") (pin "1") (pinfunction "1_1") (pintype "passive"))
      (node (ref "R109") (pin "2") (pinfunction "2_2") (pintype "passive"))
      (node (ref "R123") (pin "1") (pinfunction "1_1") (pintype "passive"))
      (node (ref "R124") (pin "1") (pinfunction "1_1") (pintype "passive"))
      (node (ref "R125") (pin "1") (pinfunction "1_1") (pintype "passive"))
      (node (ref "R126") (pin "1") (pinfunction "1_1") (pintype "passive"))
      (node (ref "R127") (pin "1") (pinfunction "1_1") (pintype "passive"))
      (node (ref "R128") (pin "1") (pinfunction "1_1") (pintype "passive"))
      (node (ref "R129") (pin "1") (pinfunction "1_1") (pintype "passive"))
      (node (ref "R130") (pin "1") (pinfunction "1_1") (pintype "passive"))
      (node (ref "R133") (pin "1") (pinfunction "1_1") (pintype "passive"))
      (node (ref "R136") (pin "1") (pinfunction "1_1") (pintype "passive"))
      (node (ref "R139") (pin "1") (pinfunction "1_1") (pintype "passive"))
      (node (ref "R140") (pin "2") (pinfunction "2_2") (pintype "passive"))
      (node (ref "R141") (pin "2") (pinfunction "2_2") (pintype "passive"))
      (node (ref "R142") (pin "1") (pinfunction "1_1") (pintype "passive"))
      (node (ref "R143") (pin "1") (pinfunction "1_1") (pintype "passive"))
      (node (ref "U101") (pin "19") (pinfunction "DGND_19") (pintype "power_in"))
      (node (ref "U101") (pin "3") (pinfunction "DGND_3") (pintype "power_in"))
      (node (ref "U101") (pin "4") (pinfunction "AGND_4") (pintype "power_in"))
      (node (ref "U101") (pin "6") (pinfunction "VSS_6") (pintype "power_in"))
    )
    (net (code "69") (name "Net-(C105-Pad1)") (class "Default")
      (node (ref "C105") (pin "1") (pinfunction "1_1") (pintype "passive"))
      (node (ref "C106") (pin "1") (pinfunction "1_1") (pintype "passive"))
      (node (ref "C107") (pin "1") (pinfunction "1_1") (pintype "passive"))
      (node (ref "R109") (pin "1") (pinfunction "1_1") (pintype "passive"))
      (node (ref "R140") (pin "1") (pinfunction "1_1") (pintype "passive"))
      (node (ref "R141") (pin "1") (pinfunction "1_1") (pintype "passive"))
    )
    (net (code "70") (name "Net-(C105-Pad2)") (class "Default")
      (node (ref "C105") (pin "2") (pinfunction "2_2") (pintype "passive"))
      (node (ref "L101") (pin "2") (pinfunction "2_2") (pintype "passive"))
      (node (ref "R105") (pin "1") (pinfunction "1_1") (pintype "passive"))
    )
    (net (code "71") (name "Net-(C106-Pad2)") (class "Default")
      (node (ref "C106") (pin "2") (pinfunction "2_2") (pintype "passive"))
      (node (ref "L102") (pin "2") (pinfunction "2_2") (pintype "passive"))
      (node (ref "R106") (pin "1") (pinfunction "1_1") (pintype "passive"))
    )
    (net (code "72") (name "Net-(C107-Pad2)") (class "Default")
      (node (ref "C107") (pin "2") (pinfunction "2_2") (pintype "passive"))
      (node (ref "L103") (pin "2") (pinfunction "2_2") (pintype "passive"))
      (node (ref "R107") (pin "1") (pinfunction "1_1") (pintype "passive"))
    )
    (net (code "73") (name "Net-(C108-Pad1)") (class "Default")
      (node (ref "C108") (pin "1") (pinfunction "1_1") (pintype "passive"))
      (node (ref "R113") (pin "1") (pinfunction "1_1") (pintype "passive"))
      (node (ref "R143") (pin "2") (pinfunction "2_2") (pintype "passive"))
    )
    (net (code "74") (name "Net-(C109-Pad1)") (class "Default")
      (node (ref "C109") (pin "1") (pinfunction "1_1") (pintype "passive"))
      (node (ref "R116") (pin "1") (pinfunction "1_1") (pintype "passive"))
      (node (ref "R139") (pin "2") (pinfunction "2_2") (pintype "passive"))
    )
    (net (code "75") (name "Net-(C110-Pad1)") (class "Default")
      (node (ref "C110") (pin "1") (pinfunction "1_1") (pintype "passive"))
      (node (ref "R119") (pin "1") (pinfunction "1_1") (pintype "passive"))
      (node (ref "R142") (pin "2") (pinfunction "2_2") (pintype "passive"))
    )
    (net (code "76") (name "Net-(D102-C)") (class "Default")
      (node (ref "C129") (pin "2") (pinfunction "2_2") (pintype "passive"))
      (node (ref "C130") (pin "2") (pinfunction "2_2") (pintype "passive"))
      (node (ref "C131") (pin "1") (pinfunction "1_1") (pintype "passive"))
      (node (ref "C132") (pin "1") (pinfunction "1_1") (pintype "passive"))
      (node (ref "D101") (pin "1") (pinfunction "A_1") (pintype "passive"))
      (node (ref "D101") (pin "2") (pinfunction "A_2") (pintype "passive"))
      (node (ref "D102") (pin "3") (pinfunction "C_3") (pintype "passive"))
      (node (ref "D103") (pin "1") (pinfunction "A_1") (pintype "passive"))
      (node (ref "D103") (pin "2") (pinfunction "A_2") (pintype "passive"))
      (node (ref "D104") (pin "3") (pinfunction "C_3") (pintype "passive"))
      (node (ref "D105") (pin "1") (pinfunction "A_1") (pintype "passive"))
      (node (ref "D105") (pin "2") (pinfunction "A_2") (pintype "passive"))
      (node (ref "D106") (pin "3") (pinfunction "C_3") (pintype "passive"))
    )
    (net (code "77") (name "Net-(P103-Pad1)") (class "Default")
      (node (ref "P103") (pin "1") (pintype "passive"))
      (node (ref "R105") (pin "4") (pinfunction "4_4") (pintype "passive"))
      (node (ref "R112") (pin "2") (pinfunction "2_2") (pintype "passive"))
    )
    (net (code "78") (name "Net-(P104-Pad1)") (class "Default")
      (node (ref "P104") (pin "1") (pintype "passive"))
      (node (ref "R106") (pin "4") (pinfunction "4_4") (pintype "passive"))
      (node (ref "R115") (pin "2") (pinfunction "2_2") (pintype "passive"))
    )
    (net (code "79") (name "Net-(P105-Pad1)") (class "Default")
      (node (ref "P105") (pin "1") (pintype "passive"))
      (node (ref "R107") (pin "4") (pinfunction "4_4") (pintype "passive"))
      (node (ref "R118") (pin "2") (pinfunction "2_2") (pintype "passive"))
    )
    (net (code "80") (name "Net-(Q101-D)") (class "Default")
      (node (ref "C129") (pin "1") (pinfunction "1_1") (pintype "passive"))
      (node (ref "C130") (pin "1") (pinfunction "1_1") (pintype "passive"))
      (node (ref "Q101") (pin "3") (pinfunction "D_3") (pintype "passive"))
      (node (ref "Q105") (pin "3") (pinfunction "D_3") (pintype "passive"))
      (node (ref "Q109") (pin "3") (pinfunction "D_3") (pintype "passive"))
      (node (ref "R101") (pin "4") (pinfunction "4_4") (pintype "passive"))
      (node (ref "R102") (pin "2") (pinfunction "2_2") (pintype "passive"))
    )
    (net (code "81") (name "Net-(R102-Pad1)") (class "Default")
      (node (ref "R102") (pin "1") (pinfunction "1_1") (pintype "passive"))
      (node (ref "R103") (pin "2") (pinfunction "2_2") (pintype "passive"))
      (node (ref "R104") (pin "2") (pinfunction "2_2") (pintype "passive"))
    )
    (net (code "82") (name "Net-(R112-Pad1)") (class "Default")
      (node (ref "R112") (pin "1") (pinfunction "1_1") (pintype "passive"))
      (node (ref "R113") (pin "2") (pinfunction "2_2") (pintype "passive"))
      (node (ref "R114") (pin "2") (pinfunction "2_2") (pintype "passive"))
    )
    (net (code "83") (name "Net-(R115-Pad1)") (class "Default")
      (node (ref "R115") (pin "1") (pinfunction "1_1") (pintype "passive"))
      (node (ref "R116") (pin "2") (pinfunction "2_2") (pintype "passive"))
      (node (ref "R117") (pin "2") (pinfunction "2_2") (pintype "passive"))
    )
    (net (code "84") (name "Net-(R118-Pad1)") (class "Default")
      (node (ref "R118") (pin "1") (pinfunction "1_1") (pintype "passive"))
      (node (ref "R119") (pin "2") (pinfunction "2_2") (pintype "passive"))
      (node (ref "R120") (pin "2") (pinfunction "2_2") (pintype "passive"))
    )
    (net (code "85") (name "Net-(R135-TOP)") (class "Default")
      (node (ref "R134") (pin "1") (pinfunction "1_1") (pintype "passive"))
      (node (ref "R135") (pin "1") (pinfunction "TOP_1") (pintype "passive"))
    )
    (net (code "86") (name "Net-(R138-TOP)") (class "Default")
      (node (ref "R137") (pin "1") (pinfunction "1_1") (pintype "passive"))
      (node (ref "R138") (pin "1") (pinfunction "TOP_1") (pintype "passive"))
    )
    (net (code "87") (name "Net-(U101-REFIN{slash}OUT)") (class "Default")
      (node (ref "C120") (pin "2") (pinfunction "2_2") (pintype "passive"))
      (node (ref "U101") (pin "5") (pinfunction "REFIN/OUT_5") (pintype "bidirectional"))
    )
    (net (code "88") (name "Net-(U102-ADJ)") (class "Default")
      (node (ref "R133") (pin "2") (pinfunction "2_2") (pintype "passive"))
      (node (ref "R134") (pin "2") (pinfunction "2_2") (pintype "passive"))
      (node (ref "U102") (pin "3") (pinfunction "ADJ_3") (pintype "power_in"))
    )
    (net (code "89") (name "Net-(U103-ADJ)") (class "Default")
      (node (ref "R136") (pin "2") (pinfunction "2_2") (pintype "passive"))
      (node (ref "R137") (pin "2") (pinfunction "2_2") (pintype "passive"))
      (node (ref "U103") (pin "3") (pinfunction "ADJ_3") (pintype "power_in"))
    )
  )
)
